# debug.net
KiCad netlist of a schematic drawn in Altium Designer
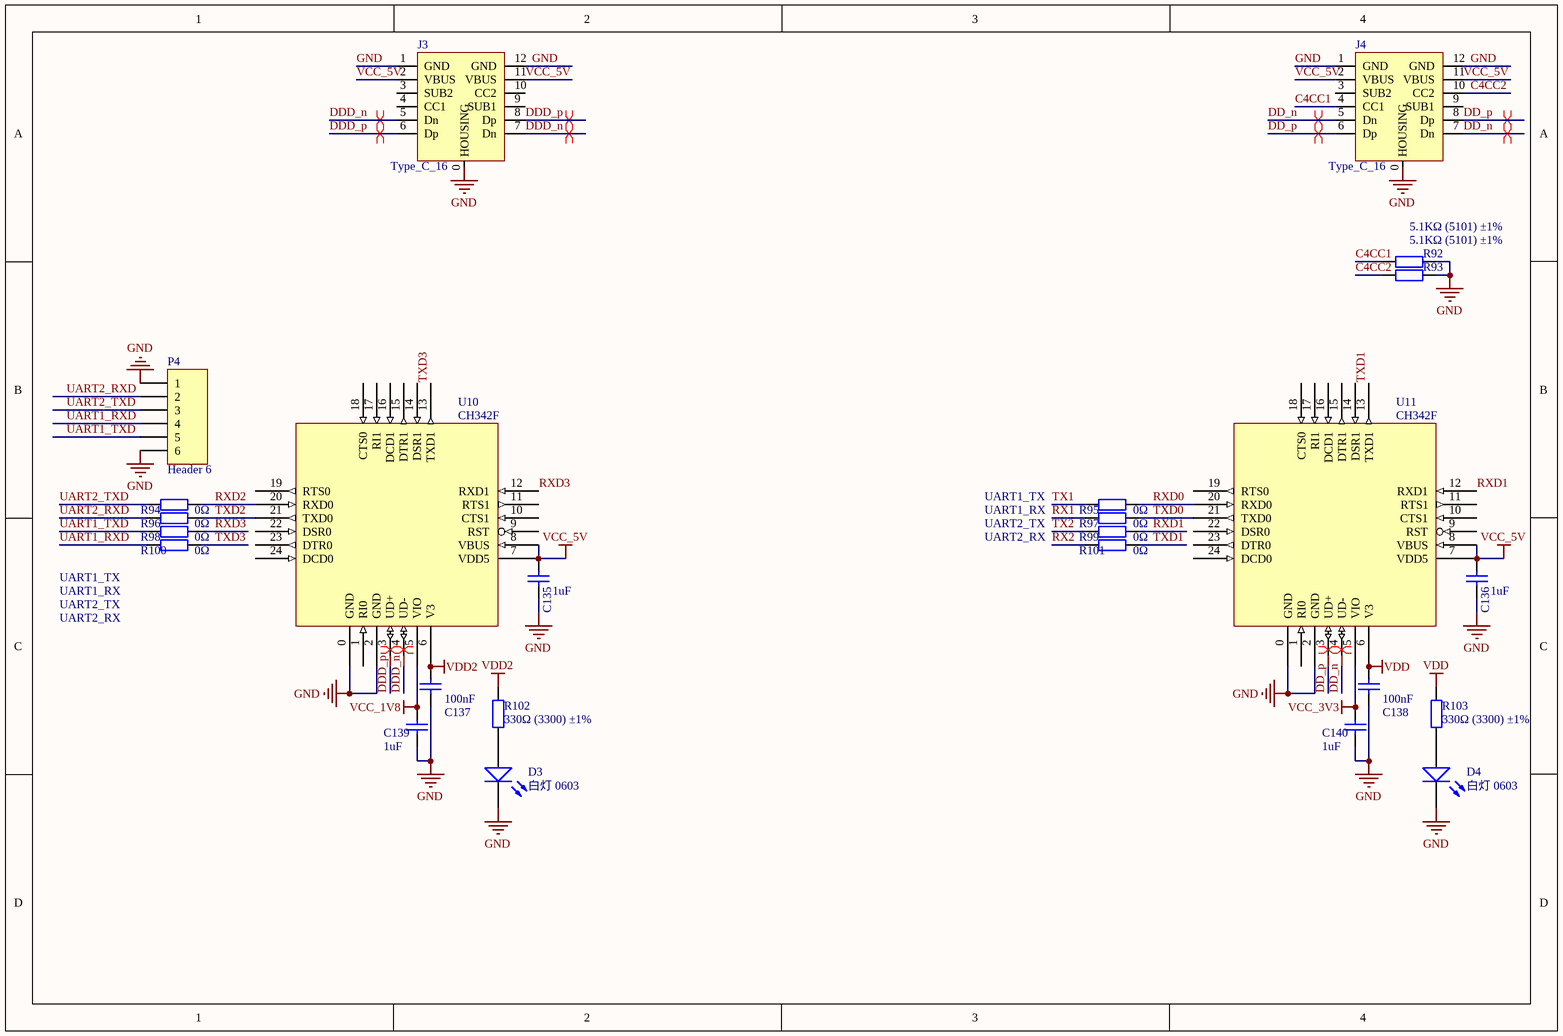
[diagram p0: debug.SchDoc]

(export (version "E")
  (design (tool "Eeschema 10.0.6"))
  (components
    (comp (ref "C135")
      (value "1uF")
      (footprint "0805_C")
      (description "贴片电容")
      (libsource (lib "嘉立创标准库") (part "0603 1uF (105) 10% 50V"))
    )
    (comp (ref "C136")
      (value "1uF")
      (footprint "0402_C")
      (description "贴片电容")
      (libsource (lib "嘉立创标准库") (part "0603 1uF (105) 10% 50V"))
    )
    (comp (ref "C137")
      (value "100nF")
      (footprint "0805_C")
      (description "贴片电容")
      (libsource (lib "嘉立创标准库") (part "0402 100nF (104) 10% 16V"))
    )
    (comp (ref "C138")
      (value "100nF")
      (footprint "0402_C")
      (description "贴片电容")
      (libsource (lib "嘉立创标准库") (part "0402 100nF (104) 10% 16V"))
    )
    (comp (ref "C139")
      (value "1uF")
      (footprint "0805_C")
      (description "贴片电容")
      (libsource (lib "嘉立创标准库") (part "0603 1uF (105) 10% 50V"))
    )
    (comp (ref "C140")
      (value "1uF")
      (footprint "0402_C")
      (description "贴片电容")
      (libsource (lib "嘉立创标准库") (part "0603 1uF (105) 10% 50V"))
    )
    (comp (ref "D3")
      (value "白灯 0603")
      (footprint "0805_LED_S1")
      (description "发光二极管")
      (libsource (lib "嘉立创标准库") (part "0603 白灯"))
    )
    (comp (ref "D4")
      (value "白灯 0603")
      (footprint "0805_LED_S1")
      (description "发光二极管")
      (libsource (lib "嘉立创标准库") (part "0603 白灯"))
    )
    (comp (ref "J3")
      (value "Type_C_16")
      (footprint "USB type C  16pin")
      (description "USB type C 16pin")
      (libsource (lib "yy_tech") (part "Type_C_16"))
    )
    (comp (ref "J4")
      (value "Type_C_16")
      (footprint "USB type C  16pin")
      (description "USB type C 16pin")
      (libsource (lib "yy_tech") (part "Type_C_16"))
    )
    (comp (ref "P4")
      (value "Header 6")
      (footprint "HDR1X6")
      (description "Header, 6-Pin")
      (fields (field (name "PUBLISHER") "Altium Limited"))
      (libsource (lib "Miscellaneous Connectors") (part "Header 6"))
    )
    (comp (ref "R92")
      (value "5.1KΩ (5101) ±1%")
      (footprint "0402_R")
      (description "贴片电阻")
      (libsource (lib "嘉立创标准库") (part "0402 5.1KΩ (5101) 1%"))
    )
    (comp (ref "R93")
      (value "5.1KΩ (5101) ±1%")
      (footprint "0402_R")
      (description "贴片电阻")
      (libsource (lib "嘉立创标准库") (part "0402 5.1KΩ (5101) 1%"))
    )
    (comp (ref "R94")
      (value "0Ω")
      (footprint "0805_R")
      (description "贴片电阻")
      (libsource (lib "Miscellaneous Devices LC") (part "0805 0Ω (0R0) 1%"))
    )
    (comp (ref "R95")
      (value "0Ω")
      (footprint "0805_R")
      (description "贴片电阻")
      (libsource (lib "Miscellaneous Devices LC") (part "0805 0Ω (0R0) 1%"))
    )
    (comp (ref "R96")
      (value "0Ω")
      (footprint "0805_R")
      (description "贴片电阻")
      (libsource (lib "Miscellaneous Devices LC") (part "0805 0Ω (0R0) 1%"))
    )
    (comp (ref "R97")
      (value "0Ω")
      (footprint "0805_R")
      (description "贴片电阻")
      (libsource (lib "Miscellaneous Devices LC") (part "0805 0Ω (0R0) 1%"))
    )
    (comp (ref "R98")
      (value "0Ω")
      (footprint "0805_R")
      (description "贴片电阻")
      (libsource (lib "Miscellaneous Devices LC") (part "0805 0Ω (0R0) 1%"))
    )
    (comp (ref "R99")
      (value "0Ω")
      (footprint "0805_R")
      (description "贴片电阻")
      (libsource (lib "Miscellaneous Devices LC") (part "0805 0Ω (0R0) 1%"))
    )
    (comp (ref "R100")
      (value "0Ω")
      (footprint "0805_R")
      (description "贴片电阻")
      (libsource (lib "Miscellaneous Devices LC") (part "0805 0Ω (0R0) 1%"))
    )
    (comp (ref "R101")
      (value "0Ω")
      (footprint "0805_R")
      (description "贴片电阻")
      (libsource (lib "Miscellaneous Devices LC") (part "0805 0Ω (0R0) 1%"))
    )
    (comp (ref "R102")
      (value "330Ω (3300) ±1%")
      (footprint "0805_R")
      (description "贴片电阻")
      (libsource (lib "Miscellaneous Devices LC") (part "0402 330Ω (3300) 1%"))
    )
    (comp (ref "R103")
      (value "330Ω (3300) ±1%")
      (footprint "0805_R")
      (description "贴片电阻")
      (libsource (lib "Miscellaneous Devices LC") (part "0402 330Ω (3300) 1%"))
    )
    (comp (ref "U10")
      (value "CH342F")
      (footprint "QFN24_4X4")
      (description "USB to dual enhanced TTL Serial / 2*UART")
      (libsource (lib "CHXXX") (part "CH342F"))
    )
    (comp (ref "U11")
      (value "CH342F")
      (footprint "QFN24_4X4")
      (description "USB to dual enhanced TTL Serial / 2*UART")
      (libsource (lib "CHXXX") (part "CH342F"))
    )
  )
  (nets
    (net (code "1") (name "/C4CC1") (class "Default")
      (node (ref "J4") (pin "4") (pinfunction "CC1_4") (pintype "passive"))
      (node (ref "R92") (pin "2") (pinfunction "2_2") (pintype "passive"))
    )
    (net (code "2") (name "/C4CC2") (class "Default")
      (node (ref "J4") (pin "10") (pinfunction "CC2_10") (pintype "passive"))
      (node (ref "R93") (pin "2") (pinfunction "2_2") (pintype "passive"))
    )
    (net (code "3") (name "/DDD_n") (class "Default")
      (node (ref "J3") (pin "5") (pinfunction "Dn_5") (pintype "passive"))
      (node (ref "J3") (pin "7") (pinfunction "Dn_7") (pintype "passive"))
      (node (ref "U10") (pin "4") (pinfunction "UD-_4") (pintype "bidirectional"))
    )
    (net (code "4") (name "/DDD_p") (class "Default")
      (node (ref "J3") (pin "6") (pinfunction "Dp_6") (pintype "passive"))
      (node (ref "J3") (pin "8") (pinfunction "Dp_8") (pintype "passive"))
      (node (ref "U10") (pin "3") (pinfunction "UD+_3") (pintype "bidirectional"))
    )
    (net (code "5") (name "/DD_n") (class "Default")
      (node (ref "J4") (pin "5") (pinfunction "Dn_5") (pintype "passive"))
      (node (ref "J4") (pin "7") (pinfunction "Dn_7") (pintype "passive"))
      (node (ref "U11") (pin "4") (pinfunction "UD-_4") (pintype "bidirectional"))
    )
    (net (code "6") (name "/DD_p") (class "Default")
      (node (ref "J4") (pin "6") (pinfunction "Dp_6") (pintype "passive"))
      (node (ref "J4") (pin "8") (pinfunction "Dp_8") (pintype "passive"))
      (node (ref "U11") (pin "3") (pinfunction "UD+_3") (pintype "bidirectional"))
    )
    (net (code "7") (name "/RX1") (class "Default")
      (node (ref "R97") (pin "1") (pinfunction "1_1") (pintype "passive"))
    )
    (net (code "8") (name "/RX2") (class "Default")
      (node (ref "R101") (pin "1") (pinfunction "1_1") (pintype "passive"))
    )
    (net (code "9") (name "/RXD0") (class "Default")
      (node (ref "R95") (pin "2") (pinfunction "2_2") (pintype "passive"))
      (node (ref "U11") (pin "20") (pinfunction "RXD0_20") (pintype "input"))
    )
    (net (code "10") (name "/RXD1") (class "Default")
      (node (ref "R99") (pin "2") (pinfunction "2_2") (pintype "passive"))
      (node (ref "U11") (pin "12") (pinfunction "RXD1_12") (pintype "input"))
    )
    (net (code "11") (name "/RXD2") (class "Default")
      (node (ref "R94") (pin "2") (pinfunction "2_2") (pintype "passive"))
      (node (ref "U10") (pin "20") (pinfunction "RXD0_20") (pintype "input"))
    )
    (net (code "12") (name "/RXD3") (class "Default")
      (node (ref "R98") (pin "2") (pinfunction "2_2") (pintype "passive"))
      (node (ref "U10") (pin "12") (pinfunction "RXD1_12") (pintype "input"))
    )
    (net (code "13") (name "/TX1") (class "Default")
      (node (ref "R95") (pin "1") (pinfunction "1_1") (pintype "passive"))
    )
    (net (code "14") (name "/TX2") (class "Default")
      (node (ref "R99") (pin "1") (pinfunction "1_1") (pintype "passive"))
    )
    (net (code "15") (name "/TXD0") (class "Default")
      (node (ref "R97") (pin "2") (pinfunction "2_2") (pintype "passive"))
      (node (ref "U11") (pin "21") (pinfunction "TXD0_21") (pintype "output"))
    )
    (net (code "16") (name "/TXD1") (class "Default")
      (node (ref "R101") (pin "2") (pinfunction "2_2") (pintype "passive"))
      (node (ref "U11") (pin "13") (pinfunction "TXD1_13") (pintype "output"))
    )
    (net (code "17") (name "/TXD2") (class "Default")
      (node (ref "R96") (pin "2") (pinfunction "2_2") (pintype "passive"))
      (node (ref "U10") (pin "21") (pinfunction "TXD0_21") (pintype "output"))
    )
    (net (code "18") (name "/TXD3") (class "Default")
      (node (ref "R100") (pin "2") (pinfunction "2_2") (pintype "passive"))
      (node (ref "U10") (pin "13") (pinfunction "TXD1_13") (pintype "output"))
    )
    (net (code "19") (name "/UART1_RXD") (class "Default")
      (node (ref "P4") (pin "4") (pinfunction "4_4") (pintype "passive"))
      (node (ref "R100") (pin "1") (pinfunction "1_1") (pintype "passive"))
    )
    (net (code "20") (name "/UART1_TXD") (class "Default")
      (node (ref "P4") (pin "5") (pinfunction "5_5") (pintype "passive"))
      (node (ref "R98") (pin "1") (pinfunction "1_1") (pintype "passive"))
    )
    (net (code "21") (name "/UART2_RXD") (class "Default")
      (node (ref "P4") (pin "2") (pinfunction "2_2") (pintype "passive"))
      (node (ref "R96") (pin "1") (pinfunction "1_1") (pintype "passive"))
    )
    (net (code "22") (name "/UART2_TXD") (class "Default")
      (node (ref "P4") (pin "3") (pinfunction "3_3") (pintype "passive"))
      (node (ref "R94") (pin "1") (pinfunction "1_1") (pintype "passive"))
    )
    (net (code "23") (name "GND") (class "Default")
      (node (ref "C135") (pin "1") (pinfunction "1_1") (pintype "passive"))
      (node (ref "C136") (pin "1") (pinfunction "1_1") (pintype "passive"))
      (node (ref "C137") (pin "1") (pinfunction "1_1") (pintype "passive"))
      (node (ref "C138") (pin "1") (pinfunction "1_1") (pintype "passive"))
      (node (ref "C139") (pin "1") (pinfunction "1_1") (pintype "passive"))
      (node (ref "C140") (pin "1") (pinfunction "1_1") (pintype "passive"))
      (node (ref "D3") (pin "K") (pinfunction "K_K") (pintype "passive"))
      (node (ref "D4") (pin "K") (pinfunction "K_K") (pintype "passive"))
      (node (ref "J3") (pin "0") (pinfunction "HOUSING_0") (pintype "passive"))
      (node (ref "J3") (pin "1") (pinfunction "GND_1") (pintype "passive"))
      (node (ref "J3") (pin "12") (pinfunction "GND_12") (pintype "passive"))
      (node (ref "J4") (pin "0") (pinfunction "HOUSING_0") (pintype "passive"))
      (node (ref "J4") (pin "1") (pinfunction "GND_1") (pintype "passive"))
      (node (ref "J4") (pin "12") (pinfunction "GND_12") (pintype "passive"))
      (node (ref "P4") (pin "1") (pinfunction "1_1") (pintype "passive"))
      (node (ref "P4") (pin "6") (pinfunction "6_6") (pintype "passive"))
      (node (ref "R92") (pin "1") (pinfunction "1_1") (pintype "passive"))
      (node (ref "R93") (pin "1") (pinfunction "1_1") (pintype "passive"))
      (node (ref "U10") (pin "0") (pinfunction "GND_0") (pintype "power_in"))
      (node (ref "U10") (pin "2") (pinfunction "GND_2") (pintype "power_in"))
      (node (ref "U11") (pin "0") (pinfunction "GND_0") (pintype "power_in"))
      (node (ref "U11") (pin "2") (pinfunction "GND_2") (pintype "power_in"))
    )
    (net (code "24") (name "Net-(D3-PadA)") (class "Default")
      (node (ref "D3") (pin "A") (pinfunction "A_A") (pintype "passive"))
      (node (ref "R102") (pin "1") (pinfunction "1_1") (pintype "passive"))
    )
    (net (code "25") (name "Net-(D4-PadA)") (class "Default")
      (node (ref "D4") (pin "A") (pinfunction "A_A") (pintype "passive"))
      (node (ref "R103") (pin "1") (pinfunction "1_1") (pintype "passive"))
    )
    (net (code "26") (name "VCC_1V8") (class "Default")
      (node (ref "C139") (pin "2") (pinfunction "2_2") (pintype "passive"))
      (node (ref "U10") (pin "5") (pinfunction "VIO_5") (pintype "power_in"))
    )
    (net (code "27") (name "VCC_3V3") (class "Default")
      (node (ref "C140") (pin "2") (pinfunction "2_2") (pintype "passive"))
      (node (ref "U11") (pin "5") (pinfunction "VIO_5") (pintype "power_in"))
    )
    (net (code "28") (name "VCC_5V") (class "Default")
      (node (ref "C135") (pin "2") (pinfunction "2_2") (pintype "passive"))
      (node (ref "C136") (pin "2") (pinfunction "2_2") (pintype "passive"))
      (node (ref "J3") (pin "11") (pinfunction "VBUS_11") (pintype "passive"))
      (node (ref "J3") (pin "2") (pinfunction "VBUS_2") (pintype "passive"))
      (node (ref "J4") (pin "11") (pinfunction "VBUS_11") (pintype "passive"))
      (node (ref "J4") (pin "2") (pinfunction "VBUS_2") (pintype "passive"))
      (node (ref "U10") (pin "7") (pinfunction "VDD5_7") (pintype "power_in"))
      (node (ref "U10") (pin "8") (pinfunction "VBUS_8") (pintype "input"))
      (node (ref "U11") (pin "7") (pinfunction "VDD5_7") (pintype "power_in"))
      (node (ref "U11") (pin "8") (pinfunction "VBUS_8") (pintype "input"))
    )
    (net (code "29") (name "VDD") (class "Default")
      (node (ref "C138") (pin "2") (pinfunction "2_2") (pintype "passive"))
      (node (ref "R103") (pin "2") (pinfunction "2_2") (pintype "passive"))
      (node (ref "U11") (pin "6") (pinfunction "V3_6") (pintype "power_in"))
    )
    (net (code "30") (name "VDD2") (class "Default")
      (node (ref "C137") (pin "2") (pinfunction "2_2") (pintype "passive"))
      (node (ref "R102") (pin "2") (pinfunction "2_2") (pintype "passive"))
      (node (ref "U10") (pin "6") (pinfunction "V3_6") (pintype "power_in"))
    )
    (net (code "31") (name "unconnected-(J3-CC1-Pad4)") (class "Default")
      (node (ref "J3") (pin "4") (pinfunction "CC1_4") (pintype "passive"))
    )
    (net (code "32") (name "unconnected-(J3-CC2-Pad10)") (class "Default")
      (node (ref "J3") (pin "10") (pinfunction "CC2_10") (pintype "passive"))
    )
    (net (code "33") (name "unconnected-(J3-SUB1-Pad9)") (class "Default")
      (node (ref "J3") (pin "9") (pinfunction "SUB1_9") (pintype "passive"))
    )
    (net (code "34") (name "unconnected-(J3-SUB2-Pad3)") (class "Default")
      (node (ref "J3") (pin "3") (pinfunction "SUB2_3") (pintype "passive"))
    )
    (net (code "35") (name "unconnected-(J4-SUB1-Pad9)") (class "Default")
      (node (ref "J4") (pin "9") (pinfunction "SUB1_9") (pintype "passive"))
    )
    (net (code "36") (name "unconnected-(J4-SUB2-Pad3)") (class "Default")
      (node (ref "J4") (pin "3") (pinfunction "SUB2_3") (pintype "passive"))
    )
    (net (code "37") (name "unconnected-(U10-CTS0-Pad18)") (class "Default")
      (node (ref "U10") (pin "18") (pinfunction "CTS0_18") (pintype "input"))
    )
    (net (code "38") (name "unconnected-(U10-CTS1-Pad10)") (class "Default")
      (node (ref "U10") (pin "10") (pinfunction "CTS1_10") (pintype "input"))
    )
    (net (code "39") (name "unconnected-(U10-DCD0-Pad24)") (class "Default")
      (node (ref "U10") (pin "24") (pinfunction "DCD0_24") (pintype "input"))
    )
    (net (code "40") (name "unconnected-(U10-DCD1-Pad16)") (class "Default")
      (node (ref "U10") (pin "16") (pinfunction "DCD1_16") (pintype "input"))
    )
    (net (code "41") (name "unconnected-(U10-DSR0-Pad22)") (class "Default")
      (node (ref "U10") (pin "22") (pinfunction "DSR0_22") (pintype "input"))
    )
    (net (code "42") (name "unconnected-(U10-DSR1-Pad14)") (class "Default")
      (node (ref "U10") (pin "14") (pinfunction "DSR1_14") (pintype "input"))
    )
    (net (code "43") (name "unconnected-(U10-DTR0-Pad23)") (class "Default")
      (node (ref "U10") (pin "23") (pinfunction "DTR0_23") (pintype "output"))
    )
    (net (code "44") (name "unconnected-(U10-DTR1-Pad15)") (class "Default")
      (node (ref "U10") (pin "15") (pinfunction "DTR1_15") (pintype "output"))
    )
    (net (code "45") (name "unconnected-(U10-RI0-Pad1)") (class "Default")
      (node (ref "U10") (pin "1") (pinfunction "RI0_1") (pintype "input"))
    )
    (net (code "46") (name "unconnected-(U10-RI1-Pad17)") (class "Default")
      (node (ref "U10") (pin "17") (pinfunction "RI1_17") (pintype "input"))
    )
    (net (code "47") (name "unconnected-(U10-RST-Pad9)") (class "Default")
      (node (ref "U10") (pin "9") (pinfunction "RST_9") (pintype "input"))
    )
    (net (code "48") (name "unconnected-(U10-RTS0-Pad19)") (class "Default")
      (node (ref "U10") (pin "19") (pinfunction "RTS0_19") (pintype "output"))
    )
    (net (code "49") (name "unconnected-(U10-RTS1-Pad11)") (class "Default")
      (node (ref "U10") (pin "11") (pinfunction "RTS1_11") (pintype "output"))
    )
    (net (code "50") (name "unconnected-(U11-CTS0-Pad18)") (class "Default")
      (node (ref "U11") (pin "18") (pinfunction "CTS0_18") (pintype "input"))
    )
    (net (code "51") (name "unconnected-(U11-CTS1-Pad10)") (class "Default")
      (node (ref "U11") (pin "10") (pinfunction "CTS1_10") (pintype "input"))
    )
    (net (code "52") (name "unconnected-(U11-DCD0-Pad24)") (class "Default")
      (node (ref "U11") (pin "24") (pinfunction "DCD0_24") (pintype "input"))
    )
    (net (code "53") (name "unconnected-(U11-DCD1-Pad16)") (class "Default")
      (node (ref "U11") (pin "16") (pinfunction "DCD1_16") (pintype "input"))
    )
    (net (code "54") (name "unconnected-(U11-DSR0-Pad22)") (class "Default")
      (node (ref "U11") (pin "22") (pinfunction "DSR0_22") (pintype "input"))
    )
    (net (code "55") (name "unconnected-(U11-DSR1-Pad14)") (class "Default")
      (node (ref "U11") (pin "14") (pinfunction "DSR1_14") (pintype "input"))
    )
    (net (code "56") (name "unconnected-(U11-DTR0-Pad23)") (class "Default")
      (node (ref "U11") (pin "23") (pinfunction "DTR0_23") (pintype "output"))
    )
    (net (code "57") (name "unconnected-(U11-DTR1-Pad15)") (class "Default")
      (node (ref "U11") (pin "15") (pinfunction "DTR1_15") (pintype "output"))
    )
    (net (code "58") (name "unconnected-(U11-RI0-Pad1)") (class "Default")
      (node (ref "U11") (pin "1") (pinfunction "RI0_1") (pintype "input"))
    )
    (net (code "59") (name "unconnected-(U11-RI1-Pad17)") (class "Default")
      (node (ref "U11") (pin "17") (pinfunction "RI1_17") (pintype "input"))
    )
    (net (code "60") (name "unconnected-(U11-RST-Pad9)") (class "Default")
      (node (ref "U11") (pin "9") (pinfunction "RST_9") (pintype "input"))
    )
    (net (code "61") (name "unconnected-(U11-RTS0-Pad19)") (class "Default")
      (node (ref "U11") (pin "19") (pinfunction "RTS0_19") (pintype "output"))
    )
    (net (code "62") (name "unconnected-(U11-RTS1-Pad11)") (class "Default")
      (node (ref "U11") (pin "11") (pinfunction "RTS1_11") (pintype "output"))
    )
  )
)
